# Schematic.net
KiCad netlist of a schematic drawn in Altium Designer
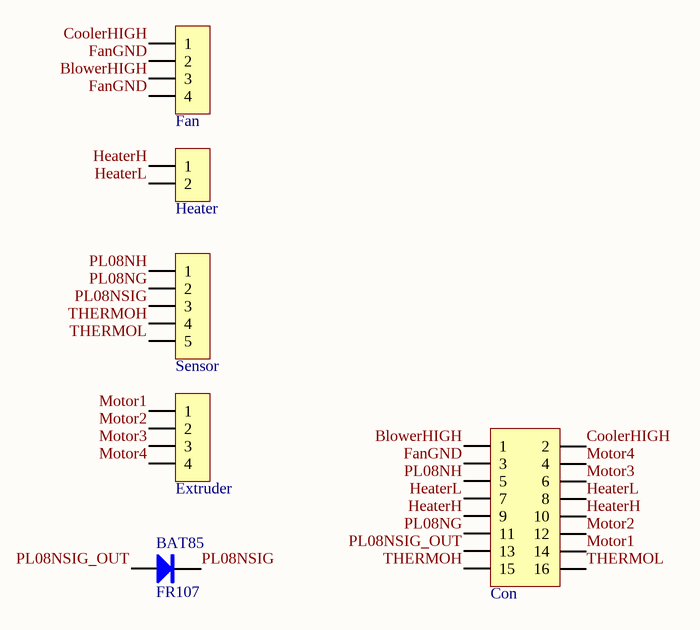
[diagram p0: Schematic.SchDoc]

(export (version "E")
  (design (tool "Eeschema 10.0.6"))
  (components
    (comp (ref "BAT85")
      (value "FR107")
      (footprint "DO-41")
      (description "快恢复整流二极管")
      (fields (field (name "版权归属") "封装库来自淘宝 ID：黄晶宝石"))
      (libsource (lib "0.2 - 二极管-整流桥") (part "FR107"))
    )
    (comp (ref "Con")
      (value "Header 8X2")
      (footprint "IDC2.54-LI-2x8P")
      (description "8*2P接插件")
      (fields (field (name "版权归属") "封装库来自淘宝 ID：黄晶宝石"))
      (libsource (lib "5.4 - 接插件-脚距2.54 (100mil) ") (part "Header 8X2"))
    )
    (comp (ref "Extruder")
      (value "HDR-1X4")
      (footprint "XH2.54-LI-4P")
      (description "4P接插件")
      (fields (field (name "版权归属") "封装库来自淘宝 ID：黄晶宝石"))
      (libsource (lib "5.4 - 接插件-脚距2.54 (100mil) ") (part "Header 4"))
    )
    (comp (ref "Fan")
      (value "HDR-1X4")
      (footprint "XH2.54-LI-4P")
      (description "4P接插件")
      (fields (field (name "版权归属") "封装库来自淘宝 ID：黄晶宝石"))
      (libsource (lib "5.4 - 接插件-脚距2.54 (100mil) ") (part "Header 4"))
    )
    (comp (ref "Heater")
      (value "HDR-1X2")
      (footprint "KF128-5.08-2P")
      (description "2P接插件")
      (fields (field (name "版权归属") "封装库来自淘宝卖家 ID：黄晶宝石"))
      (libsource (lib "6.1 - 接插件-脚距5.08 (200mil) ") (part "Header 2"))
    )
    (comp (ref "Sensor")
      (value "HDR-1X5")
      (footprint "XH2.54-LI-5P")
      (description "5P接插件")
      (fields (field (name "版权归属") "封装库来自淘宝 ID：黄晶宝石"))
      (libsource (lib "5.4 - 接插件-脚距2.54 (100mil) ") (part "Header 5"))
    )
  )
  (nets
    (net (code "1") (name "/BlowerHIGH") (class "Default")
      (node (ref "Con") (pin "1") (pinfunction "1_1") (pintype "passive"))
      (node (ref "Fan") (pin "3") (pinfunction "3_3") (pintype "passive"))
    )
    (net (code "2") (name "/CoolerHIGH") (class "Default")
      (node (ref "Con") (pin "2") (pinfunction "2_2") (pintype "passive"))
      (node (ref "Fan") (pin "1") (pinfunction "1_1") (pintype "passive"))
    )
    (net (code "3") (name "/FanGND") (class "Default")
      (node (ref "Con") (pin "3") (pinfunction "3_3") (pintype "passive"))
      (node (ref "Fan") (pin "2") (pinfunction "2_2") (pintype "passive"))
      (node (ref "Fan") (pin "4") (pinfunction "4_4") (pintype "passive"))
    )
    (net (code "4") (name "/HeaterH") (class "Default")
      (node (ref "Con") (pin "10") (pinfunction "10_10") (pintype "passive"))
      (node (ref "Con") (pin "9") (pinfunction "9_9") (pintype "passive"))
      (node (ref "Heater") (pin "1") (pinfunction "1_1") (pintype "passive"))
    )
    (net (code "5") (name "/HeaterL") (class "Default")
      (node (ref "Con") (pin "7") (pinfunction "7_7") (pintype "passive"))
      (node (ref "Con") (pin "8") (pinfunction "8_8") (pintype "passive"))
      (node (ref "Heater") (pin "2") (pinfunction "2_2") (pintype "passive"))
    )
    (net (code "6") (name "/Motor1") (class "Default")
      (node (ref "Con") (pin "14") (pinfunction "14_14") (pintype "passive"))
      (node (ref "Extruder") (pin "1") (pinfunction "1_1") (pintype "passive"))
    )
    (net (code "7") (name "/Motor2") (class "Default")
      (node (ref "Con") (pin "12") (pinfunction "12_12") (pintype "passive"))
      (node (ref "Extruder") (pin "2") (pinfunction "2_2") (pintype "passive"))
    )
    (net (code "8") (name "/Motor3") (class "Default")
      (node (ref "Con") (pin "6") (pinfunction "6_6") (pintype "passive"))
      (node (ref "Extruder") (pin "3") (pinfunction "3_3") (pintype "passive"))
    )
    (net (code "9") (name "/Motor4") (class "Default")
      (node (ref "Con") (pin "4") (pinfunction "4_4") (pintype "passive"))
      (node (ref "Extruder") (pin "4") (pinfunction "4_4") (pintype "passive"))
    )
    (net (code "10") (name "/PL08NG") (class "Default")
      (node (ref "Con") (pin "11") (pinfunction "11_11") (pintype "passive"))
      (node (ref "Sensor") (pin "2") (pinfunction "2_2") (pintype "passive"))
    )
    (net (code "11") (name "/PL08NH") (class "Default")
      (node (ref "Con") (pin "5") (pinfunction "5_5") (pintype "passive"))
      (node (ref "Sensor") (pin "1") (pinfunction "1_1") (pintype "passive"))
    )
    (net (code "12") (name "/PL08NSIG") (class "Default")
      (node (ref "BAT85") (pin "2") (pinfunction "K_2") (pintype "passive"))
      (node (ref "Sensor") (pin "3") (pinfunction "3_3") (pintype "passive"))
    )
    (net (code "13") (name "/PL08NSIG_OUT") (class "Default")
      (node (ref "BAT85") (pin "1") (pinfunction "A_1") (pintype "passive"))
      (node (ref "Con") (pin "13") (pinfunction "13_13") (pintype "passive"))
    )
    (net (code "14") (name "/THERMOH") (class "Default")
      (node (ref "Con") (pin "15") (pinfunction "15_15") (pintype "passive"))
      (node (ref "Sensor") (pin "4") (pinfunction "4_4") (pintype "passive"))
    )
    (net (code "15") (name "/THERMOL") (class "Default")
      (node (ref "Con") (pin "16") (pinfunction "16_16") (pintype "passive"))
      (node (ref "Sensor") (pin "5") (pinfunction "5_5") (pintype "passive"))
    )
  )
)
